# STM_test_board_1.net
KiCad netlist of a schematic drawn in EAGLE
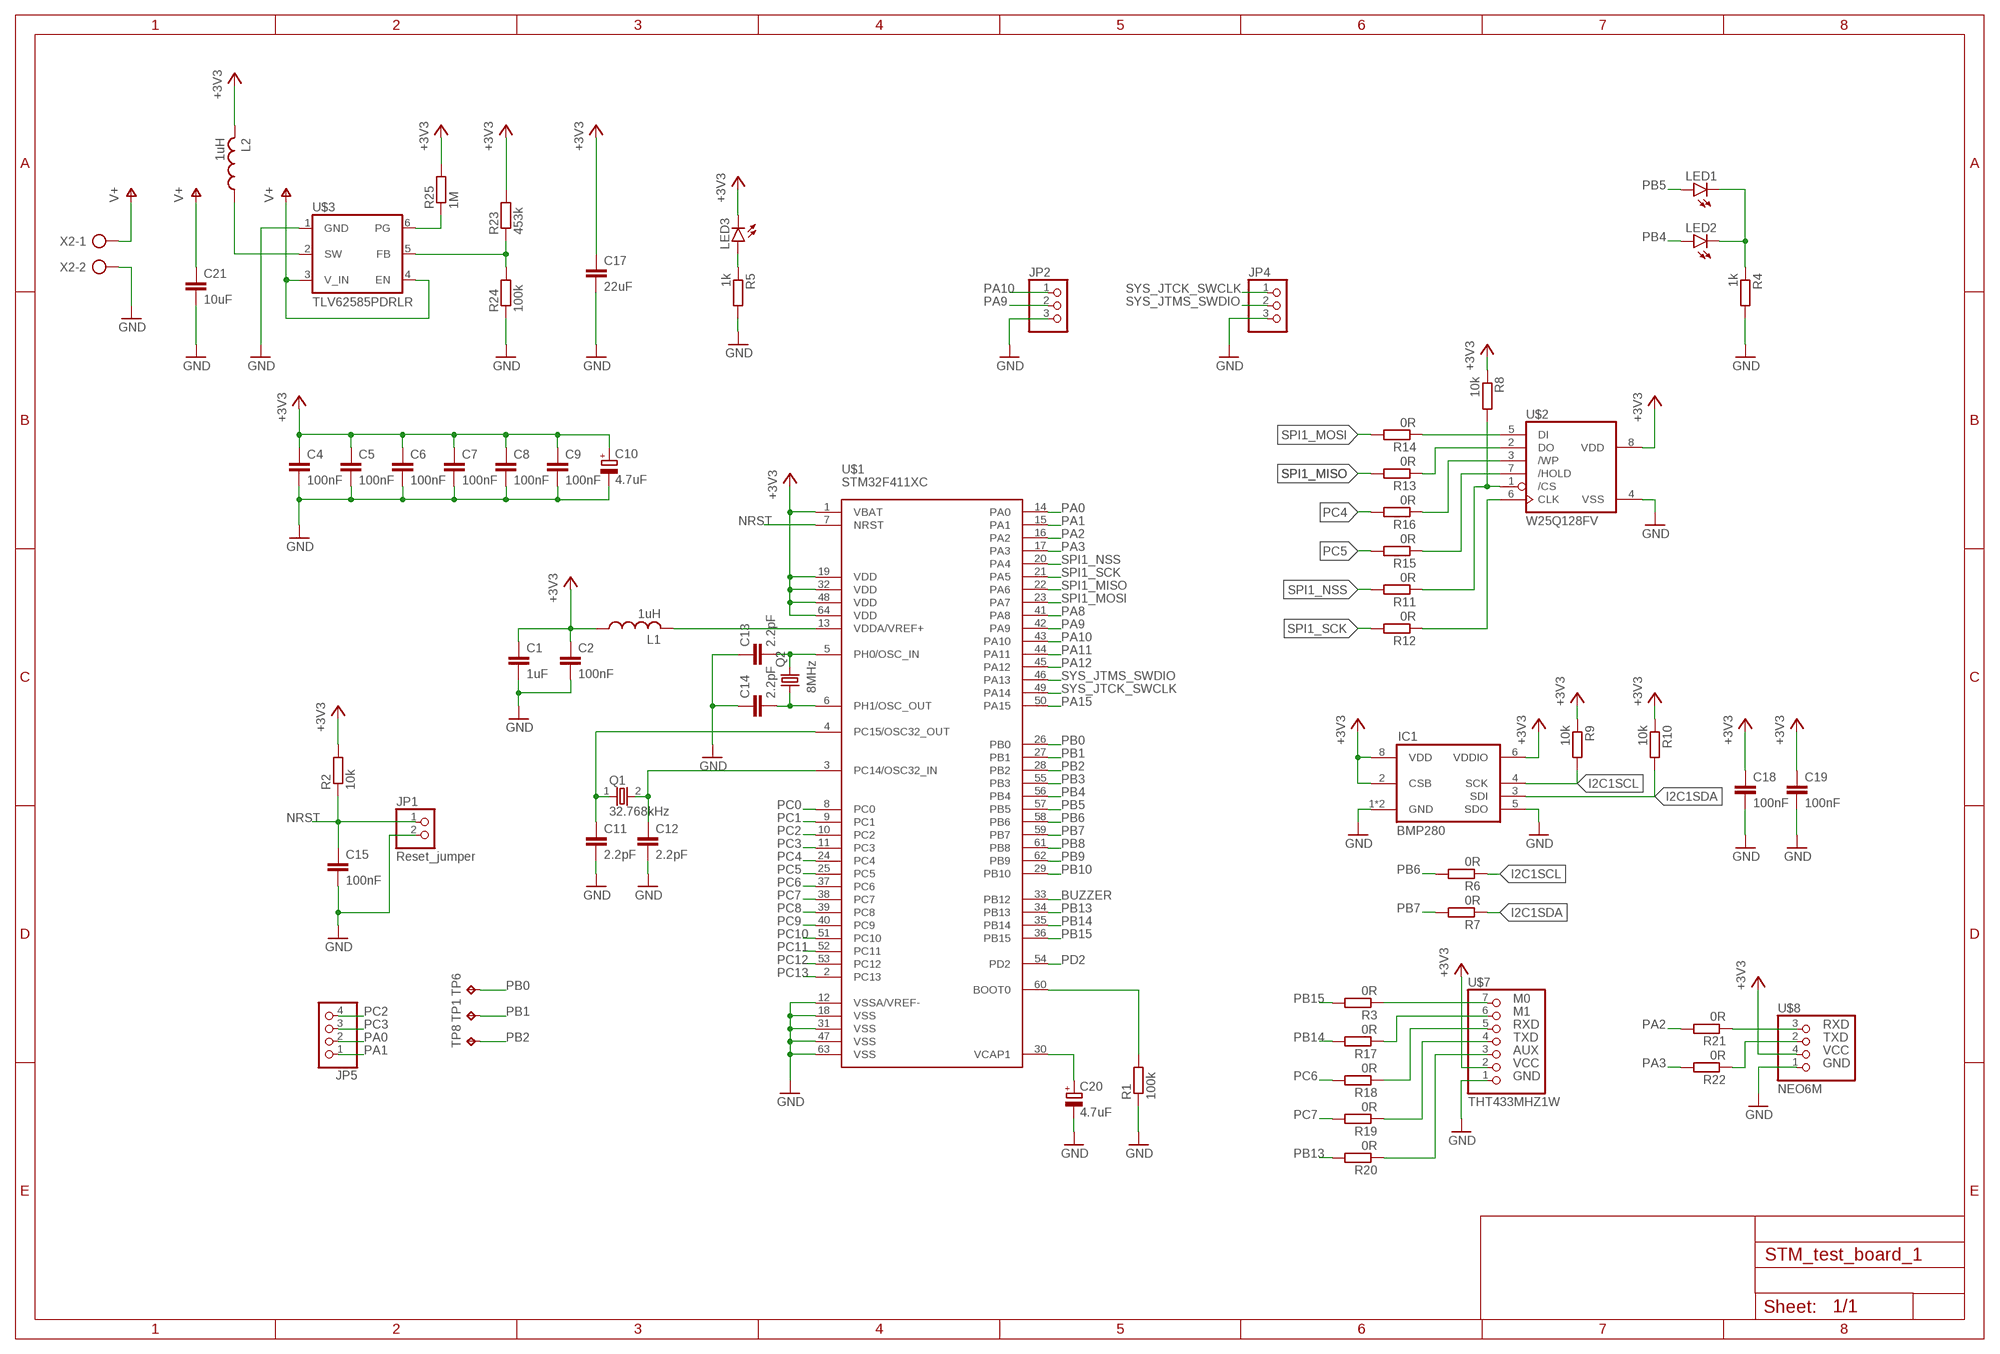
[diagram p0: schematic, sheet 1]

(export (version "E")
  (design (tool "Eeschema 10.0.6"))
  (components
    (comp (ref "C1")
      (value "1uF")
      (footprint "eagle-import:C1206")
      (libsource (lib "eagle-import") (part "rcl_334_C-EUC1206"))
    )
    (comp (ref "C2")
      (value "100nF")
      (footprint "eagle-import:C0805")
      (libsource (lib "eagle-import") (part "rcl_334_C-EUC0805"))
    )
    (comp (ref "C4")
      (value "100nF")
      (footprint "eagle-import:C0805")
      (libsource (lib "eagle-import") (part "rcl_334_C-EUC0805"))
    )
    (comp (ref "C5")
      (value "100nF")
      (footprint "eagle-import:C0805")
      (libsource (lib "eagle-import") (part "rcl_334_C-EUC0805"))
    )
    (comp (ref "C6")
      (value "100nF")
      (footprint "eagle-import:C0805")
      (libsource (lib "eagle-import") (part "rcl_334_C-EUC0805"))
    )
    (comp (ref "C7")
      (value "100nF")
      (footprint "eagle-import:C0805")
      (libsource (lib "eagle-import") (part "rcl_334_C-EUC0805"))
    )
    (comp (ref "C8")
      (value "100nF")
      (footprint "eagle-import:C0805")
      (libsource (lib "eagle-import") (part "rcl_334_C-EUC0805"))
    )
    (comp (ref "C9")
      (value "100nF")
      (footprint "eagle-import:C0805")
      (libsource (lib "eagle-import") (part "rcl_334_C-EUC0805"))
    )
    (comp (ref "C10")
      (value "4.7uF")
      (footprint "eagle-import:CT3216")
      (libsource (lib "eagle-import") (part "CPOL-EUCT3216"))
    )
    (comp (ref "C11")
      (value "2.2pF")
      (footprint "eagle-import:C0805")
      (libsource (lib "eagle-import") (part "rcl_334_C-EUC0805"))
    )
    (comp (ref "C12")
      (value "2.2pF")
      (footprint "eagle-import:C0805")
      (libsource (lib "eagle-import") (part "rcl_334_C-EUC0805"))
    )
    (comp (ref "C13")
      (value "2.2pF")
      (footprint "eagle-import:C0805")
      (libsource (lib "eagle-import") (part "rcl_334_C-EUC0805"))
    )
    (comp (ref "C14")
      (value "2.2pF")
      (footprint "eagle-import:C0805")
      (libsource (lib "eagle-import") (part "rcl_334_C-EUC0805"))
    )
    (comp (ref "C15")
      (value "100nF")
      (footprint "eagle-import:C0805")
      (libsource (lib "eagle-import") (part "C-EUC0805"))
    )
    (comp (ref "C17")
      (value "22uF")
      (footprint "eagle-import:C1206")
      (libsource (lib "eagle-import") (part "C-EUC1206"))
    )
    (comp (ref "C18")
      (value "100nF")
      (footprint "eagle-import:C0805")
      (libsource (lib "eagle-import") (part "rcl_334_C-EUC0805"))
    )
    (comp (ref "C19")
      (value "100nF")
      (footprint "eagle-import:C0805")
      (libsource (lib "eagle-import") (part "rcl_334_C-EUC0805"))
    )
    (comp (ref "C20")
      (value "4.7uF")
      (footprint "eagle-import:CT3216")
      (libsource (lib "eagle-import") (part "CPOL-EUCT3216"))
    )
    (comp (ref "C21")
      (value "10uF")
      (footprint "eagle-import:C0805")
      (libsource (lib "eagle-import") (part "C-EUC0805"))
    )
    (comp (ref "IC1")
      (value "BMP280")
      (footprint "eagle-import:BMP280")
      (libsource (lib "eagle-import") (part "BMP280"))
    )
    (comp (ref "JP1")
      (value "Reset_jumper")
      (footprint "eagle-import:1X02")
      (libsource (lib "eagle-import") (part "PINHD-1X2"))
    )
    (comp (ref "JP2")
      (value "PINHD-1X3M")
      (footprint "eagle-import:1X03M")
      (libsource (lib "eagle-import") (part "PINHD-1X3M"))
    )
    (comp (ref "JP4")
      (value "PINHD-1X3M")
      (footprint "eagle-import:1X03M")
      (libsource (lib "eagle-import") (part "PINHD-1X3M"))
    )
    (comp (ref "JP5")
      (value "PINHD-1X4M")
      (footprint "eagle-import:1X04M")
      (libsource (lib "eagle-import") (part "PINHD-1X4M"))
    )
    (comp (ref "L1")
      (value "1uH")
      (footprint "eagle-import:0207_7")
      (libsource (lib "eagle-import") (part "L-US0207/7"))
    )
    (comp (ref "L2")
      (value "1uH")
      (footprint "eagle-import:L5650M")
      (libsource (lib "eagle-import") (part "L-USL5650M"))
    )
    (comp (ref "LED1")
      (value "LEDSMT1206")
      (footprint "eagle-import:1206")
      (libsource (lib "eagle-import") (part "LEDSMT1206"))
    )
    (comp (ref "LED2")
      (value "LEDSMT1206")
      (footprint "eagle-import:1206")
      (libsource (lib "eagle-import") (part "LEDSMT1206"))
    )
    (comp (ref "LED3")
      (value "LEDSMT1206")
      (footprint "eagle-import:1206")
      (libsource (lib "eagle-import") (part "LEDSMT1206"))
    )
    (comp (ref "Q1")
      (value "32.768kHz")
      (footprint "eagle-import:MA507")
      (libsource (lib "eagle-import") (part "MA507"))
    )
    (comp (ref "Q2")
      (value "8MHz")
      (footprint "eagle-import:CTS406")
      (libsource (lib "eagle-import") (part "CRYSTALCTS406"))
    )
    (comp (ref "R1")
      (value "100k")
      (footprint "eagle-import:R0805")
      (libsource (lib "eagle-import") (part "R-EU_R0805"))
    )
    (comp (ref "R2")
      (value "10k")
      (footprint "eagle-import:R0805")
      (libsource (lib "eagle-import") (part "R-EU_R0805"))
    )
    (comp (ref "R3")
      (value "0R")
      (footprint "eagle-import:R0805")
      (libsource (lib "eagle-import") (part "R-EU_R0805"))
    )
    (comp (ref "R4")
      (value "1k")
      (footprint "eagle-import:R0805")
      (libsource (lib "eagle-import") (part "R-EU_R0805"))
    )
    (comp (ref "R5")
      (value "1k")
      (footprint "eagle-import:R0805")
      (libsource (lib "eagle-import") (part "R-EU_R0805"))
    )
    (comp (ref "R6")
      (value "0R")
      (footprint "eagle-import:R0805")
      (libsource (lib "eagle-import") (part "R-EU_R0805"))
    )
    (comp (ref "R7")
      (value "0R")
      (footprint "eagle-import:R0805")
      (libsource (lib "eagle-import") (part "R-EU_R0805"))
    )
    (comp (ref "R8")
      (value "10k")
      (footprint "eagle-import:R0805")
      (libsource (lib "eagle-import") (part "R-EU_R0805"))
    )
    (comp (ref "R9")
      (value "10k")
      (footprint "eagle-import:R0805")
      (libsource (lib "eagle-import") (part "R-EU_R0805"))
    )
    (comp (ref "R10")
      (value "10k")
      (footprint "eagle-import:R0805")
      (libsource (lib "eagle-import") (part "R-EU_R0805"))
    )
    (comp (ref "R11")
      (value "0R")
      (footprint "eagle-import:R0805")
      (libsource (lib "eagle-import") (part "R-EU_R0805"))
    )
    (comp (ref "R12")
      (value "0R")
      (footprint "eagle-import:R0805")
      (libsource (lib "eagle-import") (part "R-EU_R0805"))
    )
    (comp (ref "R13")
      (value "0R")
      (footprint "eagle-import:R0805")
      (libsource (lib "eagle-import") (part "R-EU_R0805"))
    )
    (comp (ref "R14")
      (value "0R")
      (footprint "eagle-import:R0805")
      (libsource (lib "eagle-import") (part "R-EU_R0805"))
    )
    (comp (ref "R15")
      (value "0R")
      (footprint "eagle-import:R0805")
      (libsource (lib "eagle-import") (part "R-EU_R0805"))
    )
    (comp (ref "R16")
      (value "0R")
      (footprint "eagle-import:R0805")
      (libsource (lib "eagle-import") (part "R-EU_R0805"))
    )
    (comp (ref "R17")
      (value "0R")
      (footprint "eagle-import:R0805")
      (libsource (lib "eagle-import") (part "R-EU_R0805"))
    )
    (comp (ref "R18")
      (value "0R")
      (footprint "eagle-import:R0805")
      (libsource (lib "eagle-import") (part "R-EU_R0805"))
    )
    (comp (ref "R19")
      (value "0R")
      (footprint "eagle-import:R0805")
      (libsource (lib "eagle-import") (part "R-EU_R0805"))
    )
    (comp (ref "R20")
      (value "0R")
      (footprint "eagle-import:R0805")
      (libsource (lib "eagle-import") (part "R-EU_R0805"))
    )
    (comp (ref "R21")
      (value "0R")
      (footprint "eagle-import:R0805")
      (libsource (lib "eagle-import") (part "R-EU_R0805"))
    )
    (comp (ref "R22")
      (value "0R")
      (footprint "eagle-import:R0805")
      (libsource (lib "eagle-import") (part "R-EU_R0805"))
    )
    (comp (ref "R23")
      (value "453k")
      (footprint "eagle-import:R1206")
      (libsource (lib "eagle-import") (part "R-EU_R1206"))
    )
    (comp (ref "R24")
      (value "100k")
      (footprint "eagle-import:R0805")
      (libsource (lib "eagle-import") (part "R-EU_R0805"))
    )
    (comp (ref "R25")
      (value "1M")
      (footprint "eagle-import:R1206")
      (libsource (lib "eagle-import") (part "R-EU_R1206"))
    )
    (comp (ref "TP1")
      (value "TPTP20SQ")
      (footprint "eagle-import:TP20SQ")
      (libsource (lib "eagle-import") (part "TPTP20SQ"))
    )
    (comp (ref "TP6")
      (value "TPTP20SQ")
      (footprint "eagle-import:TP20SQ")
      (libsource (lib "eagle-import") (part "TPTP20SQ"))
    )
    (comp (ref "TP8")
      (value "TPTP20SQ")
      (footprint "eagle-import:TP20SQ")
      (libsource (lib "eagle-import") (part "TPTP20SQ"))
    )
    (comp (ref "U$1")
      (value "STM32F411XC")
      (footprint "eagle-import:LQFP64")
      (libsource (lib "eagle-import") (part "STM32F411XC"))
    )
    (comp (ref "U$2")
      (value "W25Q128FV")
      (footprint "eagle-import:TSSOP-8")
      (libsource (lib "eagle-import") (part "W25Q128FV"))
    )
    (comp (ref "U$3")
      (value "TLV62585PDRLR")
      (footprint "eagle-import:SOT563")
      (libsource (lib "eagle-import") (part "TLV62585PDRLR"))
    )
    (comp (ref "U$7")
      (value "THT433MHZ1W")
      (footprint "eagle-import:E32M1000")
      (libsource (lib "eagle-import") (part "THT433MHZ1W"))
    )
    (comp (ref "U$8")
      (value "NEO6M")
      (footprint "eagle-import:1X04")
      (libsource (lib "eagle-import") (part "NEO6M"))
    )
    (comp (ref "X2")
      (value "AK300/2")
      (footprint "eagle-import:AK300_2")
      (libsource (lib "eagle-import") (part "AK300/2"))
    )
  )
  (nets
    (net (code "1") (name "+3V3") (class "Default")
      (node (ref "C1") (pin "1") (pinfunction "1_1") (pintype "passive"))
      (node (ref "C10") (pin "+") (pinfunction "+_+") (pintype "passive"))
      (node (ref "C17") (pin "1") (pinfunction "1_1") (pintype "passive"))
      (node (ref "C18") (pin "1") (pinfunction "1_1") (pintype "passive"))
      (node (ref "C19") (pin "1") (pinfunction "1_1") (pintype "passive"))
      (node (ref "C2") (pin "1") (pinfunction "1_1") (pintype "passive"))
      (node (ref "C4") (pin "1") (pinfunction "1_1") (pintype "passive"))
      (node (ref "C5") (pin "1") (pinfunction "1_1") (pintype "passive"))
      (node (ref "C6") (pin "1") (pinfunction "1_1") (pintype "passive"))
      (node (ref "C7") (pin "1") (pinfunction "1_1") (pintype "passive"))
      (node (ref "C8") (pin "1") (pinfunction "1_1") (pintype "passive"))
      (node (ref "C9") (pin "1") (pinfunction "1_1") (pintype "passive"))
      (node (ref "IC1") (pin "2") (pinfunction "CSB_2") (pintype "input"))
      (node (ref "IC1") (pin "6") (pinfunction "VDDIO_6") (pintype "power_in"))
      (node (ref "IC1") (pin "8") (pinfunction "VDD_8") (pintype "power_in"))
      (node (ref "L1") (pin "1") (pinfunction "1_1") (pintype "passive"))
      (node (ref "L2") (pin "2") (pinfunction "2_2") (pintype "passive"))
      (node (ref "LED3") (pin "C") (pinfunction "C_C") (pintype "passive"))
      (node (ref "R10") (pin "1") (pinfunction "1_1") (pintype "passive"))
      (node (ref "R2") (pin "2") (pinfunction "2_2") (pintype "passive"))
      (node (ref "R23") (pin "2") (pinfunction "2_2") (pintype "passive"))
      (node (ref "R25") (pin "2") (pinfunction "2_2") (pintype "passive"))
      (node (ref "R8") (pin "1") (pinfunction "1_1") (pintype "passive"))
      (node (ref "R9") (pin "1") (pinfunction "1_1") (pintype "passive"))
      (node (ref "U$1") (pin "1") (pinfunction "VBAT_1") (pintype "bidirectional"))
      (node (ref "U$1") (pin "19") (pinfunction "VDD_19") (pintype "bidirectional"))
      (node (ref "U$1") (pin "32") (pinfunction "VDD_32") (pintype "bidirectional"))
      (node (ref "U$1") (pin "48") (pinfunction "VDD_48") (pintype "bidirectional"))
      (node (ref "U$1") (pin "64") (pinfunction "VDD_64") (pintype "bidirectional"))
      (node (ref "U$2") (pin "8") (pinfunction "VDD_8") (pintype "power_in"))
      (node (ref "U$7") (pin "2") (pinfunction "VCC_2") (pintype "passive"))
      (node (ref "U$8") (pin "4") (pinfunction "VCC_4") (pintype "passive"))
    )
    (net (code "2") (name "/BUZZER") (class "Default")
      (node (ref "U$1") (pin "33") (pinfunction "PB12_33") (pintype "bidirectional"))
    )
    (net (code "3") (name "/NRST") (class "Default")
      (node (ref "C15") (pin "1") (pinfunction "1_1") (pintype "passive"))
      (node (ref "JP1") (pin "1") (pinfunction "1_1") (pintype "passive"))
      (node (ref "R2") (pin "1") (pinfunction "1_1") (pintype "passive"))
      (node (ref "U$1") (pin "7") (pinfunction "NRST_7") (pintype "bidirectional"))
    )
    (net (code "4") (name "/PA0") (class "Default")
      (node (ref "JP5") (pin "2") (pinfunction "2_2") (pintype "passive"))
      (node (ref "U$1") (pin "14") (pinfunction "PA0_14") (pintype "bidirectional"))
    )
    (net (code "5") (name "/PA1") (class "Default")
      (node (ref "JP5") (pin "1") (pinfunction "1_1") (pintype "passive"))
      (node (ref "U$1") (pin "15") (pinfunction "PA1_15") (pintype "bidirectional"))
    )
    (net (code "6") (name "/PA2") (class "Default")
      (node (ref "R21") (pin "2") (pinfunction "2_2") (pintype "passive"))
      (node (ref "U$1") (pin "16") (pinfunction "PA2_16") (pintype "bidirectional"))
    )
    (net (code "7") (name "/PA3") (class "Default")
      (node (ref "R22") (pin "2") (pinfunction "2_2") (pintype "passive"))
      (node (ref "U$1") (pin "17") (pinfunction "PA3_17") (pintype "bidirectional"))
    )
    (net (code "8") (name "/PA8") (class "Default")
      (node (ref "U$1") (pin "41") (pinfunction "PA8_41") (pintype "bidirectional"))
    )
    (net (code "9") (name "/PA9") (class "Default")
      (node (ref "JP2") (pin "2") (pinfunction "2_2") (pintype "passive"))
      (node (ref "U$1") (pin "42") (pinfunction "PA9_42") (pintype "bidirectional"))
    )
    (net (code "10") (name "/PA10") (class "Default")
      (node (ref "JP2") (pin "1") (pinfunction "1_1") (pintype "passive"))
      (node (ref "U$1") (pin "43") (pinfunction "PA10_43") (pintype "bidirectional"))
    )
    (net (code "11") (name "/PA11") (class "Default")
      (node (ref "U$1") (pin "44") (pinfunction "PA11_44") (pintype "bidirectional"))
    )
    (net (code "12") (name "/PA12") (class "Default")
      (node (ref "U$1") (pin "45") (pinfunction "PA12_45") (pintype "bidirectional"))
    )
    (net (code "13") (name "/PA15") (class "Default")
      (node (ref "U$1") (pin "50") (pinfunction "PA15_50") (pintype "bidirectional"))
    )
    (net (code "14") (name "/PB0") (class "Default")
      (node (ref "TP6") (pin "TP") (pinfunction "TP_TP") (pintype "input"))
      (node (ref "U$1") (pin "26") (pinfunction "PB0_26") (pintype "bidirectional"))
    )
    (net (code "15") (name "/PB1") (class "Default")
      (node (ref "TP1") (pin "TP") (pinfunction "TP_TP") (pintype "input"))
      (node (ref "U$1") (pin "27") (pinfunction "PB1_27") (pintype "bidirectional"))
    )
    (net (code "16") (name "/PB2") (class "Default")
      (node (ref "TP8") (pin "TP") (pinfunction "TP_TP") (pintype "input"))
      (node (ref "U$1") (pin "28") (pinfunction "PB2_28") (pintype "bidirectional"))
    )
    (net (code "17") (name "/PB3") (class "Default")
      (node (ref "U$1") (pin "55") (pinfunction "PB3_55") (pintype "bidirectional"))
    )
    (net (code "18") (name "/PB4") (class "Default")
      (node (ref "LED2") (pin "A") (pinfunction "A_A") (pintype "passive"))
      (node (ref "U$1") (pin "56") (pinfunction "PB4_56") (pintype "bidirectional"))
    )
    (net (code "19") (name "/PB5") (class "Default")
      (node (ref "LED1") (pin "A") (pinfunction "A_A") (pintype "passive"))
      (node (ref "U$1") (pin "57") (pinfunction "PB5_57") (pintype "bidirectional"))
    )
    (net (code "20") (name "/PB6") (class "Default")
      (node (ref "R6") (pin "2") (pinfunction "2_2") (pintype "passive"))
      (node (ref "U$1") (pin "58") (pinfunction "PB6_58") (pintype "bidirectional"))
    )
    (net (code "21") (name "/PB7") (class "Default")
      (node (ref "R7") (pin "2") (pinfunction "2_2") (pintype "passive"))
      (node (ref "U$1") (pin "59") (pinfunction "PB7_59") (pintype "bidirectional"))
    )
    (net (code "22") (name "/PB8") (class "Default")
      (node (ref "U$1") (pin "61") (pinfunction "PB8_61") (pintype "bidirectional"))
    )
    (net (code "23") (name "/PB9") (class "Default")
      (node (ref "U$1") (pin "62") (pinfunction "PB9_62") (pintype "bidirectional"))
    )
    (net (code "24") (name "/PB10") (class "Default")
      (node (ref "U$1") (pin "29") (pinfunction "PB10_29") (pintype "bidirectional"))
    )
    (net (code "25") (name "/PB13") (class "Default")
      (node (ref "R20") (pin "2") (pinfunction "2_2") (pintype "passive"))
      (node (ref "U$1") (pin "34") (pinfunction "PB13_34") (pintype "bidirectional"))
    )
    (net (code "26") (name "/PB14") (class "Default")
      (node (ref "R17") (pin "2") (pinfunction "2_2") (pintype "passive"))
      (node (ref "U$1") (pin "35") (pinfunction "PB14_35") (pintype "bidirectional"))
    )
    (net (code "27") (name "/PB15") (class "Default")
      (node (ref "R3") (pin "2") (pinfunction "2_2") (pintype "passive"))
      (node (ref "U$1") (pin "36") (pinfunction "PB15_36") (pintype "bidirectional"))
    )
    (net (code "28") (name "/PC0") (class "Default")
      (node (ref "U$1") (pin "8") (pinfunction "PC0_8") (pintype "bidirectional"))
    )
    (net (code "29") (name "/PC1") (class "Default")
      (node (ref "U$1") (pin "9") (pinfunction "PC1_9") (pintype "bidirectional"))
    )
    (net (code "30") (name "/PC2") (class "Default")
      (node (ref "JP5") (pin "4") (pinfunction "4_4") (pintype "passive"))
      (node (ref "U$1") (pin "10") (pinfunction "PC2_10") (pintype "bidirectional"))
    )
    (net (code "31") (name "/PC3") (class "Default")
      (node (ref "JP5") (pin "3") (pinfunction "3_3") (pintype "passive"))
      (node (ref "U$1") (pin "11") (pinfunction "PC3_11") (pintype "bidirectional"))
    )
    (net (code "32") (name "/PC6") (class "Default")
      (node (ref "R18") (pin "2") (pinfunction "2_2") (pintype "passive"))
      (node (ref "U$1") (pin "37") (pinfunction "PC6_37") (pintype "bidirectional"))
    )
    (net (code "33") (name "/PC7") (class "Default")
      (node (ref "R19") (pin "2") (pinfunction "2_2") (pintype "passive"))
      (node (ref "U$1") (pin "38") (pinfunction "PC7_38") (pintype "bidirectional"))
    )
    (net (code "34") (name "/PC8") (class "Default")
      (node (ref "U$1") (pin "39") (pinfunction "PC8_39") (pintype "bidirectional"))
    )
    (net (code "35") (name "/PC9") (class "Default")
      (node (ref "U$1") (pin "40") (pinfunction "PC9_40") (pintype "bidirectional"))
    )
    (net (code "36") (name "/PC10") (class "Default")
      (node (ref "U$1") (pin "51") (pinfunction "PC10_51") (pintype "bidirectional"))
    )
    (net (code "37") (name "/PC11") (class "Default")
      (node (ref "U$1") (pin "52") (pinfunction "PC11_52") (pintype "bidirectional"))
    )
    (net (code "38") (name "/PC12") (class "Default")
      (node (ref "U$1") (pin "53") (pinfunction "PC12_53") (pintype "bidirectional"))
    )
    (net (code "39") (name "/PC13") (class "Default")
      (node (ref "U$1") (pin "2") (pinfunction "PC13_2") (pintype "bidirectional"))
    )
    (net (code "40") (name "/PD2") (class "Default")
      (node (ref "U$1") (pin "54") (pinfunction "PD2_54") (pintype "bidirectional"))
    )
    (net (code "41") (name "/SYS_JTCK_SWCLK") (class "Default")
      (node (ref "JP4") (pin "1") (pinfunction "1_1") (pintype "passive"))
      (node (ref "U$1") (pin "49") (pinfunction "PA14_49") (pintype "bidirectional"))
    )
    (net (code "42") (name "/SYS_JTMS_SWDIO") (class "Default")
      (node (ref "JP4") (pin "2") (pinfunction "2_2") (pintype "passive"))
      (node (ref "U$1") (pin "46") (pinfunction "PA13_46") (pintype "bidirectional"))
    )
    (net (code "43") (name "GND") (class "Default")
      (node (ref "C1") (pin "2") (pinfunction "2_2") (pintype "passive"))
      (node (ref "C10") (pin "-") (pinfunction "-_-") (pintype "passive"))
      (node (ref "C11") (pin "2") (pinfunction "2_2") (pintype "passive"))
      (node (ref "C12") (pin "2") (pinfunction "2_2") (pintype "passive"))
      (node (ref "C13") (pin "1") (pinfunction "1_1") (pintype "passive"))
      (node (ref "C14") (pin "1") (pinfunction "1_1") (pintype "passive"))
      (node (ref "C15") (pin "2") (pinfunction "2_2") (pintype "passive"))
      (node (ref "C17") (pin "2") (pinfunction "2_2") (pintype "passive"))
      (node (ref "C18") (pin "2") (pinfunction "2_2") (pintype "passive"))
      (node (ref "C19") (pin "2") (pinfunction "2_2") (pintype "passive"))
      (node (ref "C2") (pin "2") (pinfunction "2_2") (pintype "passive"))
      (node (ref "C20") (pin "-") (pinfunction "-_-") (pintype "passive"))
      (node (ref "C21") (pin "2") (pinfunction "2_2") (pintype "passive"))
      (node (ref "C4") (pin "2") (pinfunction "2_2") (pintype "passive"))
      (node (ref "C5") (pin "2") (pinfunction "2_2") (pintype "passive"))
      (node (ref "C6") (pin "2") (pinfunction "2_2") (pintype "passive"))
      (node (ref "C7") (pin "2") (pinfunction "2_2") (pintype "passive"))
      (node (ref "C8") (pin "2") (pinfunction "2_2") (pintype "passive"))
      (node (ref "C9") (pin "2") (pinfunction "2_2") (pintype "passive"))
      (node (ref "IC1") (pin "1") (pinfunction "GND_1") (pintype "power_in"))
      (node (ref "IC1") (pin "5") (pinfunction "SDO_5") (pintype "input"))
      (node (ref "IC1") (pin "7") (pinfunction "GND_7") (pintype "power_in"))
      (node (ref "JP1") (pin "2") (pinfunction "2_2") (pintype "passive"))
      (node (ref "JP2") (pin "3") (pinfunction "3_3") (pintype "passive"))
      (node (ref "JP4") (pin "3") (pinfunction "3_3") (pintype "passive"))
      (node (ref "R1") (pin "1") (pinfunction "1_1") (pintype "passive"))
      (node (ref "R24") (pin "1") (pinfunction "1_1") (pintype "passive"))
      (node (ref "R4") (pin "2") (pinfunction "2_2") (pintype "passive"))
      (node (ref "R5") (pin "2") (pinfunction "2_2") (pintype "passive"))
      (node (ref "U$1") (pin "12") (pinfunction "VSSA/VREF-_12") (pintype "bidirectional"))
      (node (ref "U$1") (pin "18") (pinfunction "VSS_18") (pintype "bidirectional"))
      (node (ref "U$1") (pin "31") (pinfunction "VSS_31") (pintype "bidirectional"))
      (node (ref "U$1") (pin "47") (pinfunction "VSS_47") (pintype "bidirectional"))
      (node (ref "U$1") (pin "63") (pinfunction "VSS_63") (pintype "bidirectional"))
      (node (ref "U$2") (pin "4") (pinfunction "VSS_4") (pintype "power_in"))
      (node (ref "U$3") (pin "1") (pinfunction "GND_1") (pintype "input"))
      (node (ref "U$7") (pin "1") (pinfunction "GND_1") (pintype "passive"))
      (node (ref "U$8") (pin "1") (pinfunction "GND_1") (pintype "passive"))
      (node (ref "X2") (pin "2") (pinfunction "KL_2") (pintype "passive"))
    )
    (net (code "44") (name "I2C1SCL") (class "Default")
      (node (ref "IC1") (pin "4") (pinfunction "SCK_4") (pintype "bidirectional"))
      (node (ref "R6") (pin "1") (pinfunction "1_1") (pintype "passive"))
      (node (ref "R9") (pin "2") (pinfunction "2_2") (pintype "passive"))
    )
    (net (code "45") (name "I2C1SDA") (class "Default")
      (node (ref "IC1") (pin "3") (pinfunction "SDI_3") (pintype "bidirectional"))
      (node (ref "R10") (pin "2") (pinfunction "2_2") (pintype "passive"))
      (node (ref "R7") (pin "1") (pinfunction "1_1") (pintype "passive"))
    )
    (net (code "46") (name "Net-(LED1-PadC)") (class "Default")
      (node (ref "LED1") (pin "C") (pinfunction "C_C") (pintype "passive"))
      (node (ref "LED2") (pin "C") (pinfunction "C_C") (pintype "passive"))
      (node (ref "R4") (pin "1") (pinfunction "1_1") (pintype "passive"))
    )
    (net (code "47") (name "Net-(LED3-PadA)") (class "Default")
      (node (ref "LED3") (pin "A") (pinfunction "A_A") (pintype "passive"))
      (node (ref "R5") (pin "1") (pinfunction "1_1") (pintype "passive"))
    )
    (net (code "48") (name "Net-(Q2-2)") (class "Default")
      (node (ref "C13") (pin "2") (pinfunction "2_2") (pintype "passive"))
      (node (ref "Q2") (pin "3") (pinfunction "2_3") (pintype "passive"))
      (node (ref "U$1") (pin "5") (pinfunction "PH0/OSC_IN_5") (pintype "bidirectional"))
    )
    (net (code "49") (name "Net-(U$1-BOOT0)") (class "Default")
      (node (ref "R1") (pin "2") (pinfunction "2_2") (pintype "passive"))
      (node (ref "U$1") (pin "60") (pinfunction "BOOT0_60") (pintype "bidirectional"))
    )
    (net (code "50") (name "Net-(U$1-PC14{slash}OSC32_IN)") (class "Default")
      (node (ref "C12") (pin "1") (pinfunction "1_1") (pintype "passive"))
      (node (ref "Q1") (pin "2") (pinfunction "2_2") (pintype "passive"))
      (node (ref "U$1") (pin "3") (pinfunction "PC14/OSC32_IN_3") (pintype "bidirectional"))
    )
    (net (code "51") (name "Net-(U$1-PC15{slash}OSC32_OUT)") (class "Default")
      (node (ref "C11") (pin "1") (pinfunction "1_1") (pintype "passive"))
      (node (ref "Q1") (pin "1") (pinfunction "1_1") (pintype "passive"))
      (node (ref "U$1") (pin "4") (pinfunction "PC15/OSC32_OUT_4") (pintype "bidirectional"))
    )
    (net (code "52") (name "Net-(U$1-PH1{slash}OSC_OUT)") (class "Default")
      (node (ref "C14") (pin "2") (pinfunction "2_2") (pintype "passive"))
      (node (ref "Q2") (pin "1") (pinfunction "1_1") (pintype "passive"))
      (node (ref "U$1") (pin "6") (pinfunction "PH1/OSC_OUT_6") (pintype "bidirectional"))
    )
    (net (code "53") (name "Net-(U$1-VCAP1)") (class "Default")
      (node (ref "C20") (pin "+") (pinfunction "+_+") (pintype "passive"))
      (node (ref "U$1") (pin "30") (pinfunction "VCAP1_30") (pintype "bidirectional"))
    )
    (net (code "54") (name "Net-(U$1-VDDA{slash}VREF+)") (class "Default")
      (node (ref "L1") (pin "2") (pinfunction "2_2") (pintype "passive"))
      (node (ref "U$1") (pin "13") (pinfunction "VDDA/VREF+_13") (pintype "bidirectional"))
    )
    (net (code "55") (name "Net-(U$2-CLK)") (class "Default")
      (node (ref "R12") (pin "1") (pinfunction "1_1") (pintype "passive"))
      (node (ref "U$2") (pin "6") (pinfunction "CLK_6") (pintype "input"))
    )
    (net (code "56") (name "Net-(U$2-DI)") (class "Default")
      (node (ref "R14") (pin "1") (pinfunction "1_1") (pintype "passive"))
      (node (ref "U$2") (pin "5") (pinfunction "DI_5") (pintype "input"))
    )
    (net (code "57") (name "Net-(U$2-DO)") (class "Default")
      (node (ref "R13") (pin "1") (pinfunction "1_1") (pintype "passive"))
      (node (ref "U$2") (pin "2") (pinfunction "DO_2") (pintype "input"))
    )
    (net (code "58") (name "Net-(U$2-{slash}CS)") (class "Default")
      (node (ref "R11") (pin "1") (pinfunction "1_1") (pintype "passive"))
      (node (ref "R8") (pin "2") (pinfunction "2_2") (pintype "passive"))
      (node (ref "U$2") (pin "1") (pinfunction "/CS_1") (pintype "input"))
    )
    (net (code "59") (name "Net-(U$2-{slash}HOLD)") (class "Default")
      (node (ref "R15") (pin "1") (pinfunction "1_1") (pintype "passive"))
      (node (ref "U$2") (pin "7") (pinfunction "/HOLD_7") (pintype "input"))
    )
    (net (code "60") (name "Net-(U$2-{slash}WP)") (class "Default")
      (node (ref "R16") (pin "1") (pinfunction "1_1") (pintype "passive"))
      (node (ref "U$2") (pin "3") (pinfunction "/WP_3") (pintype "input"))
    )
    (net (code "61") (name "Net-(U$3-FB)") (class "Default")
      (node (ref "R23") (pin "1") (pinfunction "1_1") (pintype "passive"))
      (node (ref "R24") (pin "2") (pinfunction "2_2") (pintype "passive"))
      (node (ref "U$3") (pin "5") (pinfunction "FB_5") (pintype "input"))
    )
    (net (code "62") (name "Net-(U$3-PG)") (class "Default")
      (node (ref "R25") (pin "1") (pinfunction "1_1") (pintype "passive"))
      (node (ref "U$3") (pin "6") (pinfunction "PG_6") (pintype "output"))
    )
    (net (code "63") (name "Net-(U$3-SW)") (class "Default")
      (node (ref "L2") (pin "1") (pinfunction "1_1") (pintype "passive"))
      (node (ref "U$3") (pin "2") (pinfunction "SW_2") (pintype "input"))
    )
    (net (code "64") (name "Net-(U$7-AUX)") (class "Default")
      (node (ref "R20") (pin "1") (pinfunction "1_1") (pintype "passive"))
      (node (ref "U$7") (pin "3") (pinfunction "AUX_3") (pintype "passive"))
    )
    (net (code "65") (name "Net-(U$7-M0)") (class "Default")
      (node (ref "R3") (pin "1") (pinfunction "1_1") (pintype "passive"))
      (node (ref "U$7") (pin "7") (pinfunction "M0_7") (pintype "passive"))
    )
    (net (code "66") (name "Net-(U$7-M1)") (class "Default")
      (node (ref "R17") (pin "1") (pinfunction "1_1") (pintype "passive"))
      (node (ref "U$7") (pin "6") (pinfunction "M1_6") (pintype "passive"))
    )
    (net (code "67") (name "Net-(U$7-RXD)") (class "Default")
      (node (ref "R18") (pin "1") (pinfunction "1_1") (pintype "passive"))
      (node (ref "U$7") (pin "5") (pinfunction "RXD_5") (pintype "passive"))
    )
    (net (code "68") (name "Net-(U$7-TXD)") (class "Default")
      (node (ref "R19") (pin "1") (pinfunction "1_1") (pintype "passive"))
      (node (ref "U$7") (pin "4") (pinfunction "TXD_4") (pintype "passive"))
    )
    (net (code "69") (name "Net-(U$8-RXD)") (class "Default")
      (node (ref "R21") (pin "1") (pinfunction "1_1") (pintype "passive"))
      (node (ref "U$8") (pin "3") (pinfunction "RXD_3") (pintype "passive"))
    )
    (net (code "70") (name "Net-(U$8-TXD)") (class "Default")
      (node (ref "R22") (pin "1") (pinfunction "1_1") (pintype "passive"))
      (node (ref "U$8") (pin "2") (pinfunction "TXD_2") (pintype "passive"))
    )
    (net (code "71") (name "PC4") (class "Default")
      (node (ref "R16") (pin "2") (pinfunction "2_2") (pintype "passive"))
      (node (ref "U$1") (pin "24") (pinfunction "PC4_24") (pintype "bidirectional"))
    )
    (net (code "72") (name "PC5") (class "Default")
      (node (ref "R15") (pin "2") (pinfunction "2_2") (pintype "passive"))
      (node (ref "U$1") (pin "25") (pinfunction "PC5_25") (pintype "bidirectional"))
    )
    (net (code "73") (name "SPI1_MISO") (class "Default")
      (node (ref "R13") (pin "2") (pinfunction "2_2") (pintype "passive"))
      (node (ref "U$1") (pin "22") (pinfunction "PA6_22") (pintype "bidirectional"))
    )
    (net (code "74") (name "SPI1_MOSI") (class "Default")
      (node (ref "R14") (pin "2") (pinfunction "2_2") (pintype "passive"))
      (node (ref "U$1") (pin "23") (pinfunction "PA7_23") (pintype "bidirectional"))
    )
    (net (code "75") (name "SPI1_NSS") (class "Default")
      (node (ref "R11") (pin "2") (pinfunction "2_2") (pintype "passive"))
      (node (ref "U$1") (pin "20") (pinfunction "PA4_20") (pintype "bidirectional"))
    )
    (net (code "76") (name "SPI1_SCK") (class "Default")
      (node (ref "R12") (pin "2") (pinfunction "2_2") (pintype "passive"))
      (node (ref "U$1") (pin "21") (pinfunction "PA5_21") (pintype "bidirectional"))
    )
    (net (code "77") (name "V+") (class "Default")
      (node (ref "C21") (pin "1") (pinfunction "1_1") (pintype "passive"))
      (node (ref "U$3") (pin "3") (pinfunction "V_IN_3") (pintype "input"))
      (node (ref "U$3") (pin "4") (pinfunction "EN_4") (pintype "input"))
      (node (ref "X2") (pin "1") (pinfunction "KL_1") (pintype "passive"))
    )
  )
)
